# Revolution.net
KiCad netlist of a schematic drawn in Altium Designer
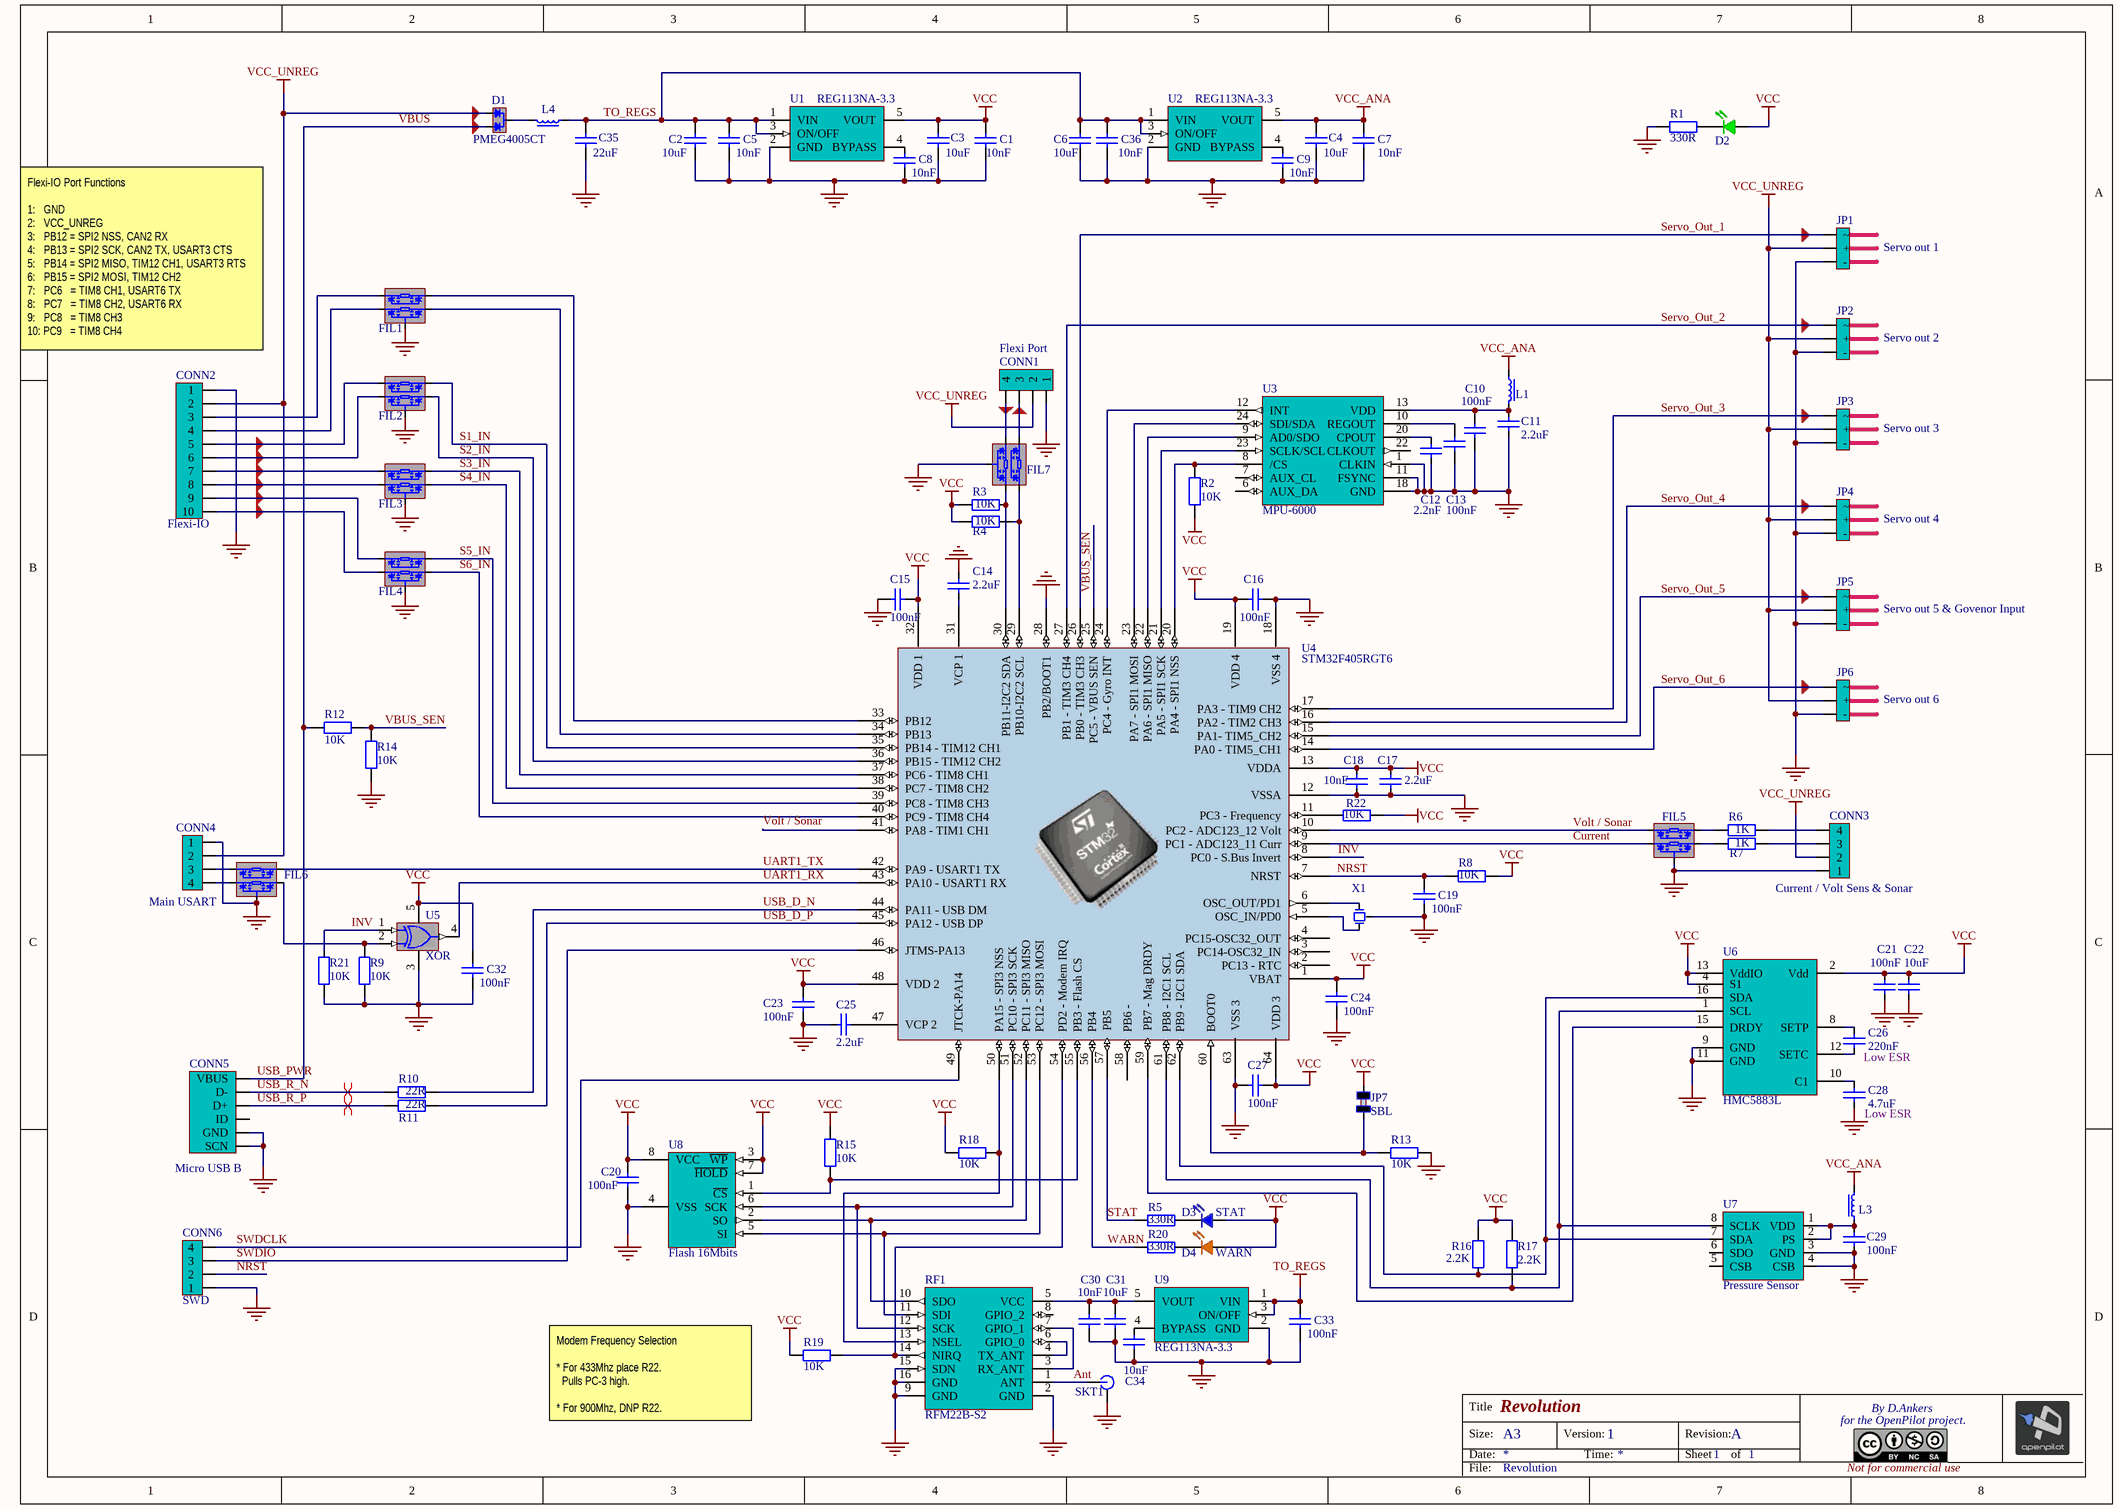
[diagram p0: Revolution.SchDoc]

(export (version "E")
  (design (tool "Eeschema 10.0.6"))
  (components
    (comp (ref "C1")
      (value "10nF")
      (footprint "CAP402N")
      (description "Capacitor SMD")
      (fields (field (name "Comment") "10n") (field (name "PUBLISHER") "The OpenPilot Project"))
      (libsource (lib "OpenPilot") (part "Cap402"))
    )
    (comp (ref "C2")
      (value "10uF")
      (footprint "CAP805L")
      (description "Capacitor SMD")
      (fields (field (name "Comment") "Cap805") (field (name "PUBLISHER") "The OpenPilot Project"))
      (libsource (lib "OpenPilot") (part "Cap805"))
    )
    (comp (ref "C3")
      (value "10uF")
      (footprint "CAP805L")
      (description "Capacitor SMD")
      (fields (field (name "Comment") "Cap805") (field (name "PUBLISHER") "The OpenPilot Project"))
      (libsource (lib "OpenPilot") (part "Cap805"))
    )
    (comp (ref "C4")
      (value "10uF")
      (footprint "CAP805L")
      (description "Capacitor SMD")
      (fields (field (name "Comment") "Cap805") (field (name "PUBLISHER") "The OpenPilot Project"))
      (libsource (lib "OpenPilot") (part "Cap805"))
    )
    (comp (ref "C5")
      (value "10nF")
      (footprint "CAP402N")
      (description "Capacitor SMD")
      (fields (field (name "Comment") "10n") (field (name "PUBLISHER") "The OpenPilot Project"))
      (libsource (lib "OpenPilot") (part "Cap402"))
    )
    (comp (ref "C6")
      (value "10uF")
      (footprint "CAP805L")
      (description "Capacitor SMD")
      (fields (field (name "Comment") "Cap805") (field (name "PUBLISHER") "The OpenPilot Project"))
      (libsource (lib "OpenPilot") (part "Cap805"))
    )
    (comp (ref "C7")
      (value "10nF")
      (footprint "CAP402N")
      (description "Capacitor SMD")
      (fields (field (name "Comment") "10n") (field (name "PUBLISHER") "The OpenPilot Project"))
      (libsource (lib "OpenPilot") (part "Cap402"))
    )
    (comp (ref "C8")
      (value "10nF")
      (footprint "CAP402N")
      (description "Capacitor SMD")
      (fields (field (name "Comment") "10n") (field (name "PUBLISHER") "The OpenPilot Project"))
      (libsource (lib "") (part "Cap402_1"))
    )
    (comp (ref "C9")
      (value "10nF")
      (footprint "CAP402N")
      (description "Capacitor SMD")
      (fields (field (name "Comment") "10n") (field (name "PUBLISHER") "The OpenPilot Project"))
      (libsource (lib "") (part "Cap402_1"))
    )
    (comp (ref "C10")
      (value "100nF")
      (footprint "CAP402N")
      (description "Capacitor SMD")
      (fields (field (name "Comment") "Cap402") (field (name "PUBLISHER") "The OpenPilot Project"))
      (libsource (lib "OpenPilot") (part "Cap402"))
    )
    (comp (ref "C11")
      (value "2.2uF")
      (footprint "CAP603L")
      (description "Capacitor SMD")
      (fields (field (name "Comment") "Cap603") (field (name "PUBLISHER") "The OpenPilot Project"))
      (libsource (lib "OpenPilot") (part "Cap603"))
    )
    (comp (ref "C12")
      (value "2.2nF")
      (footprint "CAP603L")
      (description "Capacitor SMD")
      (fields (field (name "Comment") "Cap603") (field (name "PUBLISHER") "The OpenPilot Project"))
      (libsource (lib "OpenPilot") (part "Cap603"))
    )
    (comp (ref "C13")
      (value "100nF")
      (footprint "CAP402N")
      (description "Capacitor SMD")
      (fields (field (name "Comment") "Cap402") (field (name "PUBLISHER") "The OpenPilot Project"))
      (libsource (lib "OpenPilot") (part "Cap402"))
    )
    (comp (ref "C14")
      (value "2.2uF")
      (footprint "CAP603L")
      (description "Capacitor SMD")
      (fields (field (name "Comment") "Cap603") (field (name "PUBLISHER") "The OpenPilot Project"))
      (libsource (lib "OpenPilot") (part "Cap603"))
    )
    (comp (ref "C15")
      (value "100nF")
      (footprint "CAP402N")
      (description "Capacitor SMD")
      (fields (field (name "Comment") "Cap402") (field (name "PUBLISHER") "The OpenPilot Project"))
      (libsource (lib "OpenPilot") (part "Cap402"))
    )
    (comp (ref "C16")
      (value "100nF")
      (footprint "CAP402N")
      (description "Capacitor SMD")
      (fields (field (name "Comment") "Cap402") (field (name "PUBLISHER") "The OpenPilot Project"))
      (libsource (lib "OpenPilot") (part "Cap402"))
    )
    (comp (ref "C17")
      (value "2.2uF")
      (footprint "CAP603L")
      (description "Capacitor SMD")
      (fields (field (name "Comment") "Cap603") (field (name "PUBLISHER") "The OpenPilot Project"))
      (libsource (lib "OpenPilot") (part "Cap603"))
    )
    (comp (ref "C18")
      (value "10nF")
      (footprint "CAP402N")
      (description "Capacitor SMD")
      (fields (field (name "Comment") "10n") (field (name "PUBLISHER") "The OpenPilot Project"))
      (libsource (lib "") (part "Cap402_2"))
    )
    (comp (ref "C19")
      (value "100nF")
      (footprint "CAP402N")
      (description "Capacitor SMD")
      (fields (field (name "Comment") "Cap402") (field (name "PUBLISHER") "The OpenPilot Project"))
      (libsource (lib "OpenPilot") (part "Cap402"))
    )
    (comp (ref "C20")
      (value "100nF")
      (footprint "CAP402N")
      (description "Capacitor SMD")
      (fields (field (name "Comment") "Cap402") (field (name "PUBLISHER") "The OpenPilot Project"))
      (libsource (lib "OpenPilot") (part "Cap402"))
    )
    (comp (ref "C21")
      (value "100nF")
      (footprint "CAP402N")
      (description "Capacitor SMD")
      (fields (field (name "Comment") "Cap402") (field (name "PUBLISHER") "The OpenPilot Project"))
      (libsource (lib "") (part "Cap402_2"))
    )
    (comp (ref "C22")
      (value "10uF")
      (footprint "CAP805L")
      (description "Capacitor SMD")
      (fields (field (name "Comment") "Cap805") (field (name "PUBLISHER") "The OpenPilot Project"))
      (libsource (lib "") (part "Cap805_1"))
    )
    (comp (ref "C23")
      (value "100nF")
      (footprint "CAP402N")
      (description "Capacitor SMD")
      (fields (field (name "Comment") "Cap402") (field (name "PUBLISHER") "The OpenPilot Project"))
      (libsource (lib "OpenPilot") (part "Cap402"))
    )
    (comp (ref "C24")
      (value "100nF")
      (footprint "CAP402N")
      (description "Capacitor SMD")
      (fields (field (name "Comment") "Cap402") (field (name "PUBLISHER") "The OpenPilot Project"))
      (libsource (lib "OpenPilot") (part "Cap402"))
    )
    (comp (ref "C25")
      (value "2.2uF")
      (footprint "CAP603L")
      (description "Capacitor SMD")
      (fields (field (name "Comment") "Cap603") (field (name "PUBLISHER") "The OpenPilot Project"))
      (libsource (lib "OpenPilot") (part "Cap603"))
    )
    (comp (ref "C26")
      (value "220nF")
      (footprint "CAP603L")
      (description "Capacitor SMD")
      (fields (field (name "Comment") "Cap603") (field (name "PUBLISHER") "The OpenPilot Project"))
      (libsource (lib "OpenPilot") (part "Cap603"))
    )
    (comp (ref "C27")
      (value "100nF")
      (footprint "CAP402N")
      (description "Capacitor SMD")
      (fields (field (name "Comment") "Cap402") (field (name "PUBLISHER") "The OpenPilot Project"))
      (libsource (lib "OpenPilot") (part "Cap402"))
    )
    (comp (ref "C28")
      (value "4.7uF")
      (footprint "CAP603L")
      (description "Capacitor SMD")
      (fields (field (name "Comment") "Cap603") (field (name "PUBLISHER") "The OpenPilot Project"))
      (libsource (lib "OpenPilot") (part "Cap603"))
    )
    (comp (ref "C29")
      (value "100nF")
      (footprint "CAP402N")
      (description "Capacitor SMD")
      (fields (field (name "Comment") "Cap402") (field (name "PUBLISHER") "The OpenPilot Project"))
      (libsource (lib "") (part "Cap402_2"))
    )
    (comp (ref "C30")
      (value "10nF")
      (footprint "CAP402N")
      (description "Capacitor SMD")
      (fields (field (name "Comment") "10n") (field (name "PUBLISHER") "The OpenPilot Project"))
      (libsource (lib "OpenPilot") (part "Cap402"))
    )
    (comp (ref "C31")
      (value "10uF")
      (footprint "CAP805L")
      (description "Capacitor SMD")
      (fields (field (name "Comment") "Cap805") (field (name "PUBLISHER") "The OpenPilot Project"))
      (libsource (lib "OpenPilot") (part "Cap805"))
    )
    (comp (ref "C32")
      (value "100nF")
      (footprint "CAP402N")
      (description "Capacitor SMD")
      (fields (field (name "Comment") "Cap402") (field (name "PUBLISHER") "The OpenPilot Project"))
      (libsource (lib "OpenPilot") (part "Cap402"))
    )
    (comp (ref "C33")
      (value "100nF")
      (footprint "CAP402N")
      (description "Capacitor SMD")
      (fields (field (name "Comment") "Cap402") (field (name "PUBLISHER") "The OpenPilot Project"))
      (libsource (lib "OpenPilot") (part "Cap402"))
    )
    (comp (ref "C34")
      (value "10nF")
      (footprint "CAP402N")
      (description "Capacitor SMD")
      (fields (field (name "Comment") "10n") (field (name "PUBLISHER") "The OpenPilot Project"))
      (libsource (lib "") (part "Cap402_1"))
    )
    (comp (ref "C35")
      (value "22uF")
      (footprint "CAP805L")
      (description "Capacitor SMD")
      (fields (field (name "Comment") "Cap805") (field (name "PUBLISHER") "The OpenPilot Project"))
      (libsource (lib "OpenPilot") (part "Cap805"))
    )
    (comp (ref "C36")
      (value "10nF")
      (footprint "CAP402N")
      (description "Capacitor SMD")
      (fields (field (name "Comment") "10n") (field (name "PUBLISHER") "The OpenPilot Project"))
      (libsource (lib "OpenPilot") (part "Cap402"))
    )
    (comp (ref "CONN1")
      (value "Flexi Port")
      (footprint "JST SH 4 Pin Side Entry")
      (description "JST-SH 4-pin Side Entry Socket")
      (fields (field (name "MANUFACTURER") "Generic Components"))
      (libsource (lib "") (part "JST-SH 4-pin Side Entry Socket_3"))
    )
    (comp (ref "CONN2")
      (value "Flexi-IO")
      (footprint "JST SH 10 PIN SIDE ENTRY")
      (description "JST-SH 10-pin Side Entry Socket")
      (fields (field (name "MANUFACTURER") "Generic Components"))
      (libsource (lib "OpenPilot") (part "JST-SH 10-pin Side Entry Socket"))
    )
    (comp (ref "CONN3")
      (value "Current / Volt Sens & Sonar")
      (footprint "JST SH 4 Pin Side Entry")
      (description "JST-SH 4-pin Side Entry Socket")
      (fields (field (name "MANUFACTURER") "Generic Components"))
      (libsource (lib "") (part "JST-SH 4-pin Side Entry Socket_2"))
    )
    (comp (ref "CONN4")
      (value "Main USART")
      (footprint "JST SH 4 Pin Side Entry")
      (description "JST-SH 4-pin Side Entry Socket")
      (fields (field (name "MANUFACTURER") "Generic Components"))
      (libsource (lib "") (part "JST-SH 4-pin Side Entry Socket_1"))
    )
    (comp (ref "CONN5")
      (value "Micro USB B")
      (footprint "Micro_USB")
      (description "USB Micro B SMT Socket")
      (fields (field (name "PUBLISHER") "The OpenPilot Project"))
      (libsource (lib "OpenPilot") (part "USB Micro B SMT"))
    )
    (comp (ref "CONN6")
      (value "SWD")
      (footprint "JST SH 4 Pin Side Entry")
      (description "JST-SH 4-pin Side Entry Socket")
      (fields (field (name "MANUFACTURER") "Generic Components"))
      (libsource (lib "OpenPilot") (part "JST-SH 4-pin Side Entry Socket"))
    )
    (comp (ref "D1")
      (value "PMEG4005CT")
      (footprint "SOT23-3N")
      (description "Dual Diode Command Cathode 500ma")
      (fields (field (name "PUBLISHER") "The OpenPilot Project"))
      (libsource (lib "OpenPilot") (part "PMEG4005CT"))
    )
    (comp (ref "D2")
      (value "Green")
      (footprint "LED603N")
      (description "Green 603 LED")
      (libsource (lib "OpenPilot") (part "LED 603 Gr"))
    )
    (comp (ref "D3")
      (value "STAT")
      (footprint "LED603N")
      (description "Blue 603 LED")
      (libsource (lib "OpenPilot") (part "LED 603 Bl"))
    )
    (comp (ref "D4")
      (value "WARN")
      (footprint "LED603N")
      (description "Orange 603 LED")
      (libsource (lib "OpenPilot") (part "LED 603 Or"))
    )
    (comp (ref "FIL1")
      (value "IP4256CZ5-W,115")
      (footprint "SOT-665")
      (description "IP4256CZ5-W,115 2 channel, 100R, 30pF, RF ESD Filter")
      (fields
        (field (name "MANUFACTURER") "Generic Components")
        (field (name "PUBLISHER") "The OpenPilot Project")
      )
      (libsource (lib "OpenPilot") (part "RF Filter 100R 30pF"))
    )
    (comp (ref "FIL2")
      (value "IP4256CZ5-W,115")
      (footprint "SOT-665")
      (description "IP4256CZ5-W,115 2 channel, 100R, 30pF, RF ESD Filter")
      (fields
        (field (name "MANUFACTURER") "Generic Components")
        (field (name "PUBLISHER") "The OpenPilot Project")
      )
      (libsource (lib "OpenPilot") (part "RF Filter 100R 30pF"))
    )
    (comp (ref "FIL3")
      (value "IP4256CZ5-W,115")
      (footprint "SOT-665")
      (description "IP4256CZ5-W,115 2 channel, 100R, 30pF, RF ESD Filter")
      (fields
        (field (name "MANUFACTURER") "Generic Components")
        (field (name "PUBLISHER") "The OpenPilot Project")
      )
      (libsource (lib "OpenPilot") (part "RF Filter 100R 30pF"))
    )
    (comp (ref "FIL4")
      (value "IP4256CZ5-W,115")
      (footprint "SOT-665")
      (description "IP4256CZ5-W,115 2 channel, 100R, 30pF, RF ESD Filter")
      (fields
        (field (name "MANUFACTURER") "Generic Components")
        (field (name "PUBLISHER") "The OpenPilot Project")
      )
      (libsource (lib "OpenPilot") (part "RF Filter 100R 30pF"))
    )
    (comp (ref "FIL5")
      (value "IP4256CZ5-W,115")
      (footprint "SOT-665")
      (description "IP4256CZ5-W,115 2 channel, 100R, 30pF, RF ESD Filter")
      (fields
        (field (name "MANUFACTURER") "Generic Components")
        (field (name "PUBLISHER") "The OpenPilot Project")
      )
      (libsource (lib "OpenPilot") (part "RF Filter 100R 30pF"))
    )
    (comp (ref "FIL6")
      (value "IP4256CZ5-W,115")
      (footprint "SOT-665")
      (description "IP4256CZ5-W,115 2 channel, 100R, 30pF, RF ESD Filter")
      (fields
        (field (name "MANUFACTURER") "Generic Components")
        (field (name "PUBLISHER") "The OpenPilot Project")
      )
      (libsource (lib "OpenPilot") (part "RF Filter 100R 30pF"))
    )
    (comp (ref "FIL7")
      (value "IP4256CZ5-W,115")
      (footprint "SOT-665")
      (description "IP4256CZ5-W,115 2 channel, 100R, 30pF, RF ESD Filter")
      (fields
        (field (name "MANUFACTURER") "Generic Components")
        (field (name "PUBLISHER") "The OpenPilot Project")
      )
      (libsource (lib "OpenPilot") (part "RF Filter 100R 30pF"))
    )
    (comp (ref "JP1")
      (value "Servo out 1")
      (footprint "SIP3 - 0.1")
      (description "Header, 3-Pin, 0.1\"")
      (fields (field (name "MANUFACTURER") "Generic Components"))
      (libsource (lib "OpenPilot") (part "Hdr 3 Pin 0.1"))
    )
    (comp (ref "JP2")
      (value "Servo out 2")
      (footprint "SIP3 - 0.1")
      (description "Header, 3-Pin, 0.1\"")
      (fields (field (name "MANUFACTURER") "Generic Components"))
      (libsource (lib "OpenPilot") (part "Hdr 3 Pin 0.1"))
    )
    (comp (ref "JP3")
      (value "Servo out 3")
      (footprint "SIP3 - 0.1")
      (description "Header, 3-Pin, 0.1\"")
      (fields (field (name "MANUFACTURER") "Generic Components"))
      (libsource (lib "OpenPilot") (part "Hdr 3 Pin 0.1"))
    )
    (comp (ref "JP4")
      (value "Servo out 4")
      (footprint "SIP3 - 0.1")
      (description "Header, 3-Pin, 0.1\"")
      (fields (field (name "MANUFACTURER") "Generic Components"))
      (libsource (lib "OpenPilot") (part "Hdr 3 Pin 0.1"))
    )
    (comp (ref "JP5")
      (value "Servo out 5 & Govenor Input")
      (footprint "SIP3 - 0.1")
      (description "Header, 3-Pin, 0.1\"")
      (fields (field (name "MANUFACTURER") "Generic Components"))
      (libsource (lib "OpenPilot") (part "Hdr 3 Pin 0.1"))
    )
    (comp (ref "JP6")
      (value "Servo out 6")
      (footprint "SIP3 - 0.1")
      (description "Header, 3-Pin, 0.1\"")
      (fields (field (name "MANUFACTURER") "Generic Components"))
      (libsource (lib "OpenPilot") (part "Hdr 3 Pin 0.1"))
    )
    (comp (ref "JP7")
      (value "SBL")
      (footprint "TOUCH JMP 2PAD")
      (description "2 Pad Touch Jumper")
      (fields (field (name "PUBLISHER") "The OpenPilot Project"))
      (libsource (lib "OpenPilot") (part "2 PAD Touch JMP"))
    )
    (comp (ref "L1")
      (value "FB 300mA")
      (footprint "IND603N")
      (description "Ferrite Bead 300mA")
      (fields
        (field (name "MANUFACTURER") "Generic Components")
        (field (name "PUBLISHER") "The OpenPilot Project")
      )
      (libsource (lib "OpenPilot") (part "FerriteBead 300mA"))
    )
    (comp (ref "L3")
      (value "FB 300mA")
      (footprint "IND603N")
      (description "Ferrite Bead 300mA")
      (fields
        (field (name "MANUFACTURER") "Generic Components")
        (field (name "PUBLISHER") "The OpenPilot Project")
      )
      (libsource (lib "OpenPilot") (part "FerriteBead 300mA"))
    )
    (comp (ref "L4")
      (value "FB 300mA")
      (footprint "IND603N")
      (description "Ferrite Bead 300mA")
      (fields
        (field (name "MANUFACTURER") "Generic Components")
        (field (name "PUBLISHER") "The OpenPilot Project")
      )
      (libsource (lib "OpenPilot") (part "FerriteBead 300mA"))
    )
    (comp (ref "R1")
      (value "330R")
      (footprint "RES402N")
      (description "Resistor SMD")
      (fields (field (name "Comment") "Res402") (field (name "PUBLISHER") "The OpenPilot Project"))
      (libsource (lib "") (part "Res402_1"))
    )
    (comp (ref "R2")
      (value "10K")
      (footprint "RES402N")
      (description "Resistor SMD")
      (fields (field (name "Comment") "Res402") (field (name "PUBLISHER") "The OpenPilot Project"))
      (libsource (lib "") (part "Res402_6"))
    )
    (comp (ref "R3")
      (value "10K")
      (footprint "RES402N")
      (description "Resistor SMD")
      (fields (field (name "Comment") "Res402") (field (name "PUBLISHER") "The OpenPilot Project"))
      (libsource (lib "") (part "Res402_5"))
    )
    (comp (ref "R4")
      (value "10K")
      (footprint "RES402N")
      (description "Resistor SMD")
      (fields (field (name "Comment") "Res402") (field (name "PUBLISHER") "The OpenPilot Project"))
      (libsource (lib "OpenPilot") (part "Res402"))
    )
    (comp (ref "R5")
      (value "330R")
      (footprint "RES402N")
      (description "Resistor SMD")
      (fields (field (name "Comment") "Res402") (field (name "PUBLISHER") "The OpenPilot Project"))
      (libsource (lib "OpenPilot") (part "Res402"))
    )
    (comp (ref "R6")
      (value "1K")
      (footprint "RES402N")
      (description "Resistor SMD")
      (fields (field (name "Comment") "Res402") (field (name "PUBLISHER") "The OpenPilot Project"))
      (libsource (lib "") (part "Res402_1"))
    )
    (comp (ref "R7")
      (value "1K")
      (footprint "RES402N")
      (description "Resistor SMD")
      (fields (field (name "Comment") "Res402") (field (name "PUBLISHER") "The OpenPilot Project"))
      (libsource (lib "") (part "Res402_1"))
    )
    (comp (ref "R8")
      (value "10K")
      (footprint "RES402N")
      (description "Resistor SMD")
      (fields (field (name "Comment") "Res402") (field (name "PUBLISHER") "The OpenPilot Project"))
      (libsource (lib "") (part "Res402_1"))
    )
    (comp (ref "R9")
      (value "10K")
      (footprint "RES402N")
      (description "Resistor SMD")
      (fields (field (name "Comment") "Res402") (field (name "PUBLISHER") "The OpenPilot Project"))
      (libsource (lib "") (part "Res402_6"))
    )
    (comp (ref "R10")
      (value "22R")
      (footprint "RES402N")
      (description "Resistor SMD")
      (fields (field (name "Comment") "Res402") (field (name "PUBLISHER") "The OpenPilot Project"))
      (libsource (lib "OpenPilot") (part "Res402"))
    )
    (comp (ref "R11")
      (value "22R")
      (footprint "RES402N")
      (description "Resistor SMD")
      (fields (field (name "Comment") "Res402") (field (name "PUBLISHER") "The OpenPilot Project"))
      (libsource (lib "OpenPilot") (part "Res402"))
    )
    (comp (ref "R12")
      (value "10K")
      (footprint "RES402N")
      (description "Resistor SMD")
      (fields (field (name "Comment") "Res402") (field (name "PUBLISHER") "The OpenPilot Project"))
      (libsource (lib "") (part "Res402_1"))
    )
    (comp (ref "R13")
      (value "10K")
      (footprint "RES402N")
      (description "Resistor SMD")
      (fields (field (name "Comment") "Res402") (field (name "PUBLISHER") "The OpenPilot Project"))
      (libsource (lib "") (part "Res402_1"))
    )
    (comp (ref "R14")
      (value "10K")
      (footprint "RES402N")
      (description "Resistor SMD")
      (fields (field (name "Comment") "Res402") (field (name "PUBLISHER") "The OpenPilot Project"))
      (libsource (lib "") (part "Res402_6"))
    )
    (comp (ref "R15")
      (value "10K")
      (footprint "RES402N")
      (description "Resistor SMD")
      (fields (field (name "Comment") "Res402") (field (name "PUBLISHER") "The OpenPilot Project"))
      (libsource (lib "") (part "Res402_4"))
    )
    (comp (ref "R16")
      (value "2.2K")
      (footprint "RES402N")
      (description "Resistor SMD")
      (fields (field (name "Comment") "Res402") (field (name "PUBLISHER") "The OpenPilot Project"))
      (libsource (lib "") (part "Res402_2"))
    )
    (comp (ref "R17")
      (value "2.2K")
      (footprint "RES402N")
      (description "Resistor SMD")
      (fields (field (name "Comment") "Res402") (field (name "PUBLISHER") "The OpenPilot Project"))
      (libsource (lib "") (part "Res402_4"))
    )
    (comp (ref "R18")
      (value "10K")
      (footprint "RES402N")
      (description "Resistor SMD")
      (fields (field (name "Comment") "Res402") (field (name "PUBLISHER") "The OpenPilot Project"))
      (libsource (lib "") (part "Res402_1"))
    )
    (comp (ref "R19")
      (value "10K")
      (footprint "RES402N")
      (description "Resistor SMD")
      (fields (field (name "Comment") "Res402") (field (name "PUBLISHER") "The OpenPilot Project"))
      (libsource (lib "OpenPilot") (part "Res402"))
    )
    (comp (ref "R20")
      (value "330R")
      (footprint "RES402N")
      (description "Resistor SMD")
      (fields (field (name "Comment") "Res402") (field (name "PUBLISHER") "The OpenPilot Project"))
      (libsource (lib "OpenPilot") (part "Res402"))
    )
    (comp (ref "R21")
      (value "10K")
      (footprint "RES402N")
      (description "Resistor SMD")
      (fields (field (name "Comment") "Res402") (field (name "PUBLISHER") "The OpenPilot Project"))
      (libsource (lib "") (part "Res402_3"))
    )
    (comp (ref "R22")
      (value "10K")
      (footprint "RES402N")
      (description "Resistor SMD")
      (fields (field (name "Comment") "Res402") (field (name "PUBLISHER") "The OpenPilot Project"))
      (libsource (lib "OpenPilot") (part "Res402"))
    )
    (comp (ref "RF1")
      (value "RFM22B-S2")
      (footprint "RFM22-S2")
      (description "UHF 100mW Transceiver")
      (libsource (lib "OpenPilot") (part "RFM22B-S2"))
    )
    (comp (ref "SKT1")
      (value "MMCX Thru hole")
      (footprint "MMCX_SOCKET")
      (description "MMCX Socket")
      (libsource (lib "OpenPilot") (part "MMCX Thru hole"))
    )
    (comp (ref "U1")
      (value "REG113NA-3.3")
      (footprint "SOT23-5L")
      (description "3.3V 400mA LDO Regulator")
      (libsource (lib "OpenPilot") (part "REG113NA-3.3"))
    )
    (comp (ref "U2")
      (value "REG113NA-3.3")
      (footprint "SOT23-5L")
      (description "3.3V 400mA LDO Regulator")
      (libsource (lib "OpenPilot") (part "REG113NA-3.3"))
    )
    (comp (ref "U3")
      (value "MPU-6000")
      (footprint "IMU-3000")
      (description "Invensense MPU-3/6000,  3-axis Gyros & Accel on 6000")
      (fields (field (name "MANUFACTURER") "Invensense") (field (name "PUBLISHER") "The OpenPilot Project"))
      (libsource (lib "OpenPilot") (part "MPU-3/6000"))
    )
    (comp (ref "U4")
      (value "STM32F405RGT6")
      (footprint "STM32 64 Lead")
      (description "STM32 ARM-based 32-bit MCU with 1MB Flash, 64-pin LQFP, Industrial Temperature")
      (libsource (lib "OpenPilot") (part "STM32F103RET6"))
    )
    (comp (ref "U5")
      (value "XOR")
      (footprint "DCK-5")
      (description "XOR Gate SN74LVC1G86DCKR")
      (libsource (lib "OpenPilot") (part "XOR SN74LVC1G86DCKR"))
    )
    (comp (ref "U6")
      (value "HMC5883L")
      (footprint "LPCC-16")
      (description "IC, Magnetometer, 3 axis, +/- 8 Oe, I2C, 160Hz")
      (fields (field (name "MANUFACTURER") "Honeywell") (field (name "PUBLISHER") "The OpenPilot Project"))
      (libsource (lib "OpenPilot") (part "HMC5883L"))
    )
    (comp (ref "U7")
      (value "Pressure Sensor")
      (footprint "MS5611-01BA03")
      (description "Pressure Sensor - MS5611-01BA03")
      (libsource (lib "OpenPilot") (part "MS5611-01BA03"))
    )
    (comp (ref "U8")
      (value "Flash 16Mbits")
      (footprint "SOIC8_N")
      (description "16Mbit SPI Flash Memory")
      (fields (field (name "PUBLISHER") "The OpenPilot Project"))
      (libsource (lib "OpenPilot") (part "Flash 16Mb 75MHZ 8SOIC"))
    )
    (comp (ref "U9")
      (value "REG113NA-3.3")
      (footprint "SOT23-5L")
      (description "3.3V 400mA LDO Regulator")
      (libsource (lib "") (part "REG113NA-3.3_1"))
    )
    (comp (ref "X1")
      (value "8Mhz Ceralock")
      (footprint "CERALOCK 8Mhz")
      (description "Ceralock 8Mhz with caps")
      (fields (field (name "PUBLISHER") "The OpenPilot Project"))
      (libsource (lib "OpenPilot") (part "CERALOCK8"))
    )
  )
  (nets
    (net (code "1") (name "/Ant") (class "Default")
      (node (ref "RF1") (pin "1") (pinfunction "ANT_1") (pintype "passive"))
      (node (ref "SKT1") (pin "1") (pinfunction "PIN_1") (pintype "passive"))
    )
    (net (code "2") (name "/Current") (class "Default")
      (node (ref "FIL5") (pin "1") (pinfunction "1_1") (pintype "passive"))
      (node (ref "U4") (pin "9") (pinfunction "PC1_-_ADC123_11_Curr_9") (pintype "bidirectional"))
    )
    (net (code "3") (name "/INV") (class "Default")
      (node (ref "R21") (pin "2") (pinfunction "2_2") (pintype "passive"))
      (node (ref "U4") (pin "8") (pinfunction "PC0_-_S.Bus_Invert_8") (pintype "bidirectional"))
      (node (ref "U5") (pin "1") (pinfunction "A_1") (pintype "input"))
    )
    (net (code "4") (name "/NRST") (class "Default")
      (node (ref "C19") (pin "2") (pinfunction "2_2") (pintype "passive"))
      (node (ref "CONN6") (pin "2") (pinfunction "2_2") (pintype "passive"))
      (node (ref "R8") (pin "1") (pinfunction "1_1") (pintype "passive"))
      (node (ref "U4") (pin "7") (pinfunction "NRST_7") (pintype "bidirectional"))
    )
    (net (code "5") (name "/S1_IN") (class "Default")
      (node (ref "FIL2") (pin "3") (pinfunction "3_3") (pintype "passive"))
      (node (ref "U4") (pin "35") (pinfunction "PB14_-_TIM12_CH1_35") (pintype "bidirectional"))
    )
    (net (code "6") (name "/S2_IN") (class "Default")
      (node (ref "FIL2") (pin "1") (pinfunction "1_1") (pintype "passive"))
      (node (ref "U4") (pin "36") (pinfunction "PB15_-_TIM12_CH2_36") (pintype "bidirectional"))
    )
    (net (code "7") (name "/S3_IN") (class "Default")
      (node (ref "FIL3") (pin "3") (pinfunction "3_3") (pintype "passive"))
      (node (ref "U4") (pin "37") (pinfunction "PC6_-_TIM8_CH1_37") (pintype "bidirectional"))
    )
    (net (code "8") (name "/S4_IN") (class "Default")
      (node (ref "FIL3") (pin "1") (pinfunction "1_1") (pintype "passive"))
      (node (ref "U4") (pin "38") (pinfunction "PC7_-_TIM8_CH2_38") (pintype "bidirectional"))
    )
    (net (code "9") (name "/S5_IN") (class "Default")
      (node (ref "FIL4") (pin "3") (pinfunction "3_3") (pintype "passive"))
      (node (ref "U4") (pin "39") (pinfunction "PC8_-_TIM8_CH3_39") (pintype "bidirectional"))
    )
    (net (code "10") (name "/S6_IN") (class "Default")
      (node (ref "FIL4") (pin "1") (pinfunction "1_1") (pintype "passive"))
      (node (ref "U4") (pin "40") (pinfunction "PC9_-_TIM8_CH4_40") (pintype "bidirectional"))
    )
    (net (code "11") (name "/STAT") (class "Default")
      (node (ref "R5") (pin "2") (pinfunction "2_2") (pintype "passive"))
      (node (ref "U4") (pin "57") (pinfunction "PB5_57") (pintype "bidirectional"))
    )
    (net (code "12") (name "/SWDCLK") (class "Default")
      (node (ref "CONN6") (pin "4") (pinfunction "4_4") (pintype "passive"))
      (node (ref "U4") (pin "49") (pinfunction "JTCK-PA14_49") (pintype "bidirectional"))
    )
    (net (code "13") (name "/SWDIO") (class "Default")
      (node (ref "CONN6") (pin "3") (pinfunction "3_3") (pintype "passive"))
      (node (ref "U4") (pin "46") (pinfunction "JTMS-PA13_46") (pintype "bidirectional"))
    )
    (net (code "14") (name "/Servo_Out_1") (class "Default")
      (node (ref "JP1") (pin "1") (pinfunction "~_1") (pintype "passive"))
      (node (ref "U4") (pin "26") (pinfunction "PB0_-_TIM3_CH3_26") (pintype "bidirectional"))
    )
    (net (code "15") (name "/Servo_Out_2") (class "Default")
      (node (ref "JP2") (pin "1") (pinfunction "~_1") (pintype "passive"))
      (node (ref "U4") (pin "27") (pinfunction "PB1_-_TIM3_CH4_27") (pintype "bidirectional"))
    )
    (net (code "16") (name "/Servo_Out_3") (class "Default")
      (node (ref "JP3") (pin "1") (pinfunction "~_1") (pintype "passive"))
      (node (ref "U4") (pin "17") (pinfunction "PA3_-_TIM9_CH2_17") (pintype "bidirectional"))
    )
    (net (code "17") (name "/Servo_Out_4") (class "Default")
      (node (ref "JP4") (pin "1") (pinfunction "~_1") (pintype "passive"))
      (node (ref "U4") (pin "16") (pinfunction "PA2_-_TIM2_CH3_16") (pintype "bidirectional"))
    )
    (net (code "18") (name "/Servo_Out_5") (class "Default")
      (node (ref "JP5") (pin "1") (pinfunction "~_1") (pintype "passive"))
      (node (ref "U4") (pin "15") (pinfunction "PA1-_TIM5_CH2_15") (pintype "bidirectional"))
    )
    (net (code "19") (name "/Servo_Out_6") (class "Default")
      (node (ref "JP6") (pin "1") (pinfunction "~_1") (pintype "passive"))
      (node (ref "U4") (pin "14") (pinfunction "PA0_-_TIM5_CH1_14") (pintype "bidirectional"))
    )
    (net (code "20") (name "/UART1_RX") (class "Default")
      (node (ref "U4") (pin "43") (pinfunction "PA10_-_USART1_RX_43") (pintype "bidirectional"))
      (node (ref "U5") (pin "4") (pinfunction "Y_4") (pintype "output"))
    )
    (net (code "21") (name "/UART1_TX") (class "Default")
      (node (ref "FIL6") (pin "3") (pinfunction "3_3") (pintype "passive"))
      (node (ref "U4") (pin "42") (pinfunction "PA9_-_USART1_TX_42") (pintype "bidirectional"))
    )
    (net (code "22") (name "/USB_D_N") (class "Default")
      (node (ref "R10") (pin "1") (pinfunction "1_1") (pintype "passive"))
      (node (ref "U4") (pin "44") (pinfunction "PA11_-_USB_DM_44") (pintype "bidirectional"))
    )
    (net (code "23") (name "/USB_D_P") (class "Default")
      (node (ref "R11") (pin "1") (pinfunction "1_1") (pintype "passive"))
      (node (ref "U4") (pin "45") (pinfunction "PA12_-_USB_DP_45") (pintype "bidirectional"))
    )
    (net (code "24") (name "/USB_PWR") (class "Default")
      (node (ref "CONN5") (pin "1") (pinfunction "VBUS_1") (pintype "passive"))
      (node (ref "D1") (pin "1") (pinfunction "A1_1") (pintype "passive"))
      (node (ref "R12") (pin "1") (pinfunction "1_1") (pintype "passive"))
    )
    (net (code "25") (name "/USB_R_N") (class "Default")
      (node (ref "CONN5") (pin "2") (pinfunction "D-_2") (pintype "passive"))
      (node (ref "R10") (pin "2") (pinfunction "2_2") (pintype "passive"))
    )
    (net (code "26") (name "/USB_R_P") (class "Default")
      (node (ref "CONN5") (pin "3") (pinfunction "D+_3") (pintype "passive"))
      (node (ref "R11") (pin "2") (pinfunction "2_2") (pintype "passive"))
    )
    (net (code "27") (name "/VBUS_SEN") (class "Default")
      (node (ref "R12") (pin "2") (pinfunction "2_2") (pintype "passive"))
      (node (ref "R14") (pin "2") (pinfunction "2_2") (pintype "passive"))
      (node (ref "U4") (pin "25") (pinfunction "PC5_-_VBUS_SEN_25") (pintype "bidirectional"))
    )
    (net (code "28") (name "/Volt {slash} Sonar") (class "Default")
      (node (ref "FIL5") (pin "3") (pinfunction "3_3") (pintype "passive"))
      (node (ref "U4") (pin "10") (pinfunction "PC2_-_ADC123_12_Volt_10") (pintype "bidirectional"))
      (node (ref "U4") (pin "41") (pinfunction "PA8_-_TIM1_CH1_41") (pintype "bidirectional"))
    )
    (net (code "29") (name "/WARN") (class "Default")
      (node (ref "R20") (pin "2") (pinfunction "2_2") (pintype "passive"))
      (node (ref "U4") (pin "56") (pinfunction "PB4_56") (pintype "bidirectional"))
    )
    (net (code "30") (name "GND") (class "Default")
      (node (ref "C1") (pin "2") (pinfunction "2_2") (pintype "passive"))
      (node (ref "C10") (pin "1") (pinfunction "1_1") (pintype "passive"))
      (node (ref "C11") (pin "2") (pinfunction "2_2") (pintype "passive"))
      (node (ref "C12") (pin "1") (pinfunction "1_1") (pintype "passive"))
      (node (ref "C13") (pin "2") (pinfunction "2_2") (pintype "passive"))
      (node (ref "C14") (pin "1") (pinfunction "1_1") (pintype "passive"))
      (node (ref "C15") (pin "2") (pinfunction "2_2") (pintype "passive"))
      (node (ref "C16") (pin "1") (pinfunction "1_1") (pintype "passive"))
      (node (ref "C17") (pin "1") (pinfunction "1_1") (pintype "passive"))
      (node (ref "C18") (pin "2") (pinfunction "2_2") (pintype "passive"))
      (node (ref "C19") (pin "1") (pinfunction "1_1") (pintype "passive"))
      (node (ref "C2") (pin "2") (pinfunction "2_2") (pintype "passive"))
      (node (ref "C20") (pin "1") (pinfunction "1_1") (pintype "passive"))
      (node (ref "C21") (pin "2") (pinfunction "2_2") (pintype "passive"))
      (node (ref "C22") (pin "1") (pinfunction "1_1") (pintype "passive"))
      (node (ref "C23") (pin "2") (pinfunction "2_2") (pintype "passive"))
      (node (ref "C24") (pin "1") (pinfunction "1_1") (pintype "passive"))
      (node (ref "C25") (pin "1") (pinfunction "1_1") (pintype "passive"))
      (node (ref "C27") (pin "2") (pinfunction "2_2") (pintype "passive"))
      (node (ref "C28") (pin "2") (pinfunction "2_2") (pintype "passive"))
      (node (ref "C29") (pin "2") (pinfunction "2_2") (pintype "passive"))
      (node (ref "C3") (pin "2") (pinfunction "2_2") (pintype "passive"))
      (node (ref "C30") (pin "2") (pinfunction "2_2") (pintype "passive"))
      (node (ref "C31") (pin "2") (pinfunction "2_2") (pintype "passive"))
      (node (ref "C32") (pin "2") (pinfunction "2_2") (pintype "passive"))
      (node (ref "C33") (pin "1") (pinfunction "1_1") (pintype "passive"))
      (node (ref "C34") (pin "2") (pinfunction "2_2") (pintype "passive"))
      (node (ref "C35") (pin "2") (pinfunction "2_2") (pintype "passive"))
      (node (ref "C36") (pin "2") (pinfunction "2_2") (pintype "passive"))
      (node (ref "C4") (pin "2") (pinfunction "2_2") (pintype "passive"))
      (node (ref "C5") (pin "2") (pinfunction "2_2") (pintype "passive"))
      (node (ref "C6") (pin "2") (pinfunction "2_2") (pintype "passive"))
      (node (ref "C7") (pin "2") (pinfunction "2_2") (pintype "passive"))
      (node (ref "C8") (pin "2") (pinfunction "2_2") (pintype "passive"))
      (node (ref "C9") (pin "2") (pinfunction "2_2") (pintype "passive"))
      (node (ref "CONN1") (pin "1") (pinfunction "1_1") (pintype "passive"))
      (node (ref "CONN2") (pin "1") (pinfunction "1_1") (pintype "passive"))
      (node (ref "CONN3") (pin "1") (pinfunction "1_1") (pintype "passive"))
      (node (ref "CONN4") (pin "1") (pinfunction "1_1") (pintype "passive"))
      (node (ref "CONN5") (pin "0") (pinfunction "SCN_0") (pintype "passive"))
      (node (ref "CONN5") (pin "5") (pinfunction "GND_5") (pintype "passive"))
      (node (ref "CONN6") (pin "1") (pinfunction "1_1") (pintype "passive"))
      (node (ref "FIL1") (pin "2") (pinfunction "PAD_2") (pintype "passive"))
      (node (ref "FIL2") (pin "2") (pinfunction "PAD_2") (pintype "passive"))
      (node (ref "FIL3") (pin "2") (pinfunction "PAD_2") (pintype "passive"))
      (node (ref "FIL4") (pin "2") (pinfunction "PAD_2") (pintype "passive"))
      (node (ref "FIL5") (pin "2") (pinfunction "PAD_2") (pintype "passive"))
      (node (ref "FIL6") (pin "2") (pinfunction "PAD_2") (pintype "passive"))
      (node (ref "FIL7") (pin "2") (pinfunction "PAD_2") (pintype "passive"))
      (node (ref "JP1") (pin "3") (pinfunction "-_3") (pintype "passive"))
      (node (ref "JP2") (pin "3") (pinfunction "-_3") (pintype "passive"))
      (node (ref "JP3") (pin "3") (pinfunction "-_3") (pintype "passive"))
      (node (ref "JP4") (pin "3") (pinfunction "-_3") (pintype "passive"))
      (node (ref "JP5") (pin "3") (pinfunction "-_3") (pintype "passive"))
      (node (ref "JP6") (pin "3") (pinfunction "-_3") (pintype "passive"))
      (node (ref "R1") (pin "1") (pinfunction "1_1") (pintype "passive"))
      (node (ref "R13") (pin "2") (pinfunction "2_2") (pintype "passive"))
      (node (ref "R14") (pin "1") (pinfunction "1_1") (pintype "passive"))
      (node (ref "R21") (pin "1") (pinfunction "1_1") (pintype "passive"))
      (node (ref "R9") (pin "1") (pinfunction "1_1") (pintype "passive"))
      (node (ref "RF1") (pin "15") (pinfunction "SDN_15") (pintype "input"))
      (node (ref "RF1") (pin "16") (pinfunction "GND_16") (pintype "power_in"))
      (node (ref "RF1") (pin "2") (pinfunction "GND_2") (pintype "power_in"))
      (node (ref "RF1") (pin "9") (pinfunction "GND_9") (pintype "power_in"))
      (node (ref "SKT1") (pin "2") (pinfunction "GND_2") (pintype "passive"))
      (node (ref "U1") (pin "2") (pinfunction "GND_2") (pintype "power_in"))
      (node (ref "U2") (pin "2") (pinfunction "GND_2") (pintype "power_in"))
      (node (ref "U3") (pin "1") (pinfunction "CLKIN_1") (pintype "input"))
      (node (ref "U3") (pin "11") (pinfunction "FSYNC_11") (pintype "passive"))
      (node (ref "U3") (pin "18") (pinfunction "GND_18") (pintype "power_in"))
      (node (ref "U4") (pin "12") (pinfunction "VSSA_12") (pintype "power_in"))
      (node (ref "U4") (pin "18") (pinfunction "VSS_4_18") (pintype "power_in"))
      (node (ref "U4") (pin "28") (pinfunction "PB2/BOOT1_28") (pintype "bidirectional"))
      (node (ref "U4") (pin "63") (pinfunction "VSS_3_63") (pintype "power_in"))
      (node (ref "U5") (pin "3") (pinfunction "GND_3") (pintype "power_in"))
      (node (ref "U6") (pin "11") (pinfunction "GND_11") (pintype "passive"))
      (node (ref "U6") (pin "9") (pinfunction "GND_9") (pintype "passive"))
      (node (ref "U7") (pin "3") (pinfunction "GND_3") (pintype "power_in"))
      (node (ref "U7") (pin "4") (pinfunction "CSB_4") (pintype "passive"))
      (node (ref "U8") (pin "4") (pinfunction "VSS_4") (pintype "power_in"))
      (node (ref "U9") (pin "2") (pinfunction "GND_2") (pintype "power_in"))
      (node (ref "X1") (pin "3") (pinfunction "3_3") (pintype "passive"))
    )
    (net (code "31") (name "Net-(CONN1-Pad3)") (class "Default")
      (node (ref "CONN1") (pin "3") (pinfunction "3_3") (pintype "passive"))
      (node (ref "FIL7") (pin "4") (pinfunction "4_4") (pintype "passive"))
    )
    (net (code "32") (name "Net-(CONN1-Pad4)") (class "Default")
      (node (ref "CONN1") (pin "4") (pinfunction "4_4") (pintype "passive"))
      (node (ref "FIL7") (pin "5") (pinfunction "5_5") (pintype "passive"))
    )
    (net (code "33") (name "Net-(CONN2-Pad3)") (class "Default")
      (node (ref "CONN2") (pin "3") (pinfunction "3_3") (pintype "passive"))
      (node (ref "FIL1") (pin "4") (pinfunction "4_4") (pintype "passive"))
    )
    (net (code "34") (name "Net-(CONN2-Pad4)") (class "Default")
      (node (ref "CONN2") (pin "4") (pinfunction "4_4") (pintype "passive"))
      (node (ref "FIL1") (pin "5") (pinfunction "5_5") (pintype "passive"))
    )
    (net (code "35") (name "Net-(CONN2-Pad5)") (class "Default")
      (node (ref "CONN2") (pin "5") (pinfunction "5_5") (pintype "passive"))
      (node (ref "FIL2") (pin "4") (pinfunction "4_4") (pintype "passive"))
    )
    (net (code "36") (name "Net-(CONN2-Pad6)") (class "Default")
      (node (ref "CONN2") (pin "6") (pinfunction "6_6") (pintype "passive"))
      (node (ref "FIL2") (pin "5") (pinfunction "5_5") (pintype "passive"))
    )
    (net (code "37") (name "Net-(CONN2-Pad7)") (class "Default")
      (node (ref "CONN2") (pin "7") (pinfunction "7_7") (pintype "passive"))
      (node (ref "FIL3") (pin "4") (pinfunction "4_4") (pintype "passive"))
    )
    (net (code "38") (name "Net-(CONN2-Pad8)") (class "Default")
      (node (ref "CONN2") (pin "8") (pinfunction "8_8") (pintype "passive"))
      (node (ref "FIL3") (pin "5") (pinfunction "5_5") (pintype "passive"))
    )
    (net (code "39") (name "Net-(CONN2-Pad9)") (class "Default")
      (node (ref "CONN2") (pin "9") (pinfunction "9_9") (pintype "passive"))
      (node (ref "FIL4") (pin "4") (pinfunction "4_4") (pintype "passive"))
    )
    (net (code "40") (name "Net-(CONN2-Pad10)") (class "Default")
      (node (ref "CONN2") (pin "10") (pinfunction "10_10") (pintype "passive"))
      (node (ref "FIL4") (pin "5") (pinfunction "5_5") (pintype "passive"))
    )
    (net (code "41") (name "Net-(CONN3-Pad3)") (class "Default")
      (node (ref "CONN3") (pin "3") (pinfunction "3_3") (pintype "passive"))
      (node (ref "R7") (pin "2") (pinfunction "2_2") (pintype "passive"))
    )
    (net (code "42") (name "Net-(CONN3-Pad4)") (class "Default")
      (node (ref "CONN3") (pin "4") (pinfunction "4_4") (pintype "passive"))
      (node (ref "R6") (pin "2") (pinfunction "2_2") (pintype "passive"))
    )
    (net (code "43") (name "Net-(CONN4-Pad3)") (class "Default")
      (node (ref "CONN4") (pin "3") (pinfunction "3_3") (pintype "passive"))
      (node (ref "FIL6") (pin "4") (pinfunction "4_4") (pintype "passive"))
    )
    (net (code "44") (name "Net-(CONN4-Pad4)") (class "Default")
      (node (ref "CONN4") (pin "4") (pinfunction "4_4") (pintype "passive"))
      (node (ref "FIL6") (pin "5") (pinfunction "5_5") (pintype "passive"))
    )
    (net (code "45") (name "Net-(D1-COM)") (class "Default")
      (node (ref "D1") (pin "3") (pinfunction "COM_3") (pintype "passive"))
      (node (ref "L4") (pin "2") (pinfunction "2_2") (pintype "passive"))
    )
    (net (code "46") (name "Net-(D2-K)") (class "Default")
      (node (ref "D2") (pin "1") (pinfunction "K_1") (pintype "passive"))
      (node (ref "R1") (pin "2") (pinfunction "2_2") (pintype "passive"))
    )
    (net (code "47") (name "Net-(D3-K)") (class "Default")
      (node (ref "D3") (pin "1") (pinfunction "K_1") (pintype "passive"))
      (node (ref "R5") (pin "1") (pinfunction "1_1") (pintype "passive"))
    )
    (net (code "48") (name "Net-(D4-K)") (class "Default")
      (node (ref "D4") (pin "1") (pinfunction "K_1") (pintype "passive"))
      (node (ref "R20") (pin "1") (pinfunction "1_1") (pintype "passive"))
    )
    (net (code "49") (name "Net-(FIL5-Pad4)") (class "Default")
      (node (ref "FIL5") (pin "4") (pinfunction "4_4") (pintype "passive"))
      (node (ref "R6") (pin "1") (pinfunction "1_1") (pintype "passive"))
    )
    (net (code "50") (name "Net-(FIL5-Pad5)") (class "Default")
      (node (ref "FIL5") (pin "5") (pinfunction "5_5") (pintype "passive"))
      (node (ref "R7") (pin "1") (pinfunction "1_1") (pintype "passive"))
    )
    (net (code "51") (name "Net-(RF1-GPIO_0)") (class "Default")
      (node (ref "RF1") (pin "4") (pinfunction "TX_ANT_4") (pintype "passive"))
      (node (ref "RF1") (pin "6") (pinfunction "GPIO_0_6") (pintype "bidirectional"))
    )
    (net (code "52") (name "Net-(RF1-GPIO_1)") (class "Default")
      (node (ref "RF1") (pin "3") (pinfunction "RX_ANT_3") (pintype "passive"))
      (node (ref "RF1") (pin "7") (pinfunction "GPIO_1_7") (pintype "bidirectional"))
    )
    (net (code "53") (name "Net-(RF1-NIRQ)") (class "Default")
      (node (ref "R19") (pin "1") (pinfunction "1_1") (pintype "passive"))
      (node (ref "RF1") (pin "14") (pinfunction "NIRQ_14") (pintype "output"))
      (node (ref "U4") (pin "54") (pinfunction "PD2_-_Modem_IRQ_54") (pintype "bidirectional"))
    )
    (net (code "54") (name "Net-(RF1-NSEL)") (class "Default")
      (node (ref "R18") (pin "2") (pinfunction "2_2") (pintype "passive"))
      (node (ref "RF1") (pin "13") (pinfunction "NSEL_13") (pintype "input"))
      (node (ref "U4") (pin "50") (pinfunction "PA15_-_SPI3_NSS_50") (pintype "bidirectional"))
    )
    (net (code "55") (name "Net-(RF1-SCK)") (class "Default")
      (node (ref "RF1") (pin "12") (pinfunction "SCK_12") (pintype "input"))
      (node (ref "U4") (pin "51") (pinfunction "PC10_-_SPI3_SCK_51") (pintype "bidirectional"))
      (node (ref "U8") (pin "6") (pinfunction "SCK_6") (pintype "input"))
    )
    (net (code "56") (name "Net-(RF1-SDI)") (class "Default")
      (node (ref "RF1") (pin "11") (pinfunction "SDI_11") (pintype "input"))
      (node (ref "U4") (pin "53") (pinfunction "PC12_-_SPI3_MOSI_53") (pintype "bidirectional"))
      (node (ref "U8") (pin "5") (pinfunction "SI_5") (pintype "input"))
    )
    (net (code "57") (name "Net-(RF1-SDO)") (class "Default")
      (node (ref "RF1") (pin "10") (pinfunction "SDO_10") (pintype "output"))
      (node (ref "U4") (pin "52") (pinfunction "PC11_-_SPI3_MISO_52") (pintype "bidirectional"))
      (node (ref "U8") (pin "2") (pinfunction "SO_2") (pintype "output"))
    )
    (net (code "58") (name "Net-(RF1-VCC)") (class "Default")
      (node (ref "C30") (pin "1") (pinfunction "1_1") (pintype "passive"))
      (node (ref "C31") (pin "1") (pinfunction "1_1") (pintype "passive"))
      (node (ref "RF1") (pin "5") (pinfunction "VCC_5") (pintype "power_in"))
      (node (ref "U9") (pin "5") (pinfunction "VOUT_5") (pintype "power_in"))
    )
    (net (code "59") (name "Net-(U1-BYPASS)") (class "Default")
      (node (ref "C8") (pin "1") (pinfunction "1_1") (pintype "passive"))
      (node (ref "U1") (pin "4") (pinfunction "BYPASS_4") (pintype "passive"))
    )
    (net (code "60") (name "Net-(U2-BYPASS)") (class "Default")
      (node (ref "C9") (pin "1") (pinfunction "1_1") (pintype "passive"))
      (node (ref "U2") (pin "4") (pinfunction "BYPASS_4") (pintype "passive"))
    )
    (net (code "61") (name "Net-(U3-AD0{slash}SDO)") (class "Default")
      (node (ref "U3") (pin "9") (pinfunction "AD0/SDO_9") (pintype "input"))
      (node (ref "U4") (pin "22") (pinfunction "PA6_-_SPI1_MISO_22") (pintype "bidirectional"))
    )
    (net (code "62") (name "Net-(U3-CPOUT)") (class "Default")
      (node (ref "C12") (pin "2") (pinfunction "2_2") (pintype "passive"))
      (node (ref "U3") (pin "20") (pinfunction "CPOUT_20") (pintype "passive"))
    )
    (net (code "63") (name "Net-(U3-INT)") (class "Default")
      (node (ref "U3") (pin "12") (pinfunction "INT_12") (pintype "output"))
      (node (ref "U4") (pin "24") (pinfunction "PC4_-_Gyro_INT_24") (pintype "bidirectional"))
    )
    (net (code "64") (name "Net-(U3-REGOUT)") (class "Default")
      (node (ref "C13") (pin "1") (pinfunction "1_1") (pintype "passive"))
      (node (ref "U3") (pin "10") (pinfunction "REGOUT_10") (pintype "passive"))
    )
    (net (code "65") (name "Net-(U3-SCLK{slash}SCL)") (class "Default")
      (node (ref "U3") (pin "23") (pinfunction "SCLK/SCL_23") (pintype "input"))
      (node (ref "U4") (pin "21") (pinfunction "PA5_-_SPI1_SCK_21") (pintype "bidirectional"))
    )
    (net (code "66") (name "Net-(U3-SDI{slash}SDA)") (class "Default")
      (node (ref "U3") (pin "24") (pinfunction "SDI/SDA_24") (pintype "bidirectional"))
      (node (ref "U4") (pin "23") (pinfunction "PA7_-_SPI1_MOSI_23") (pintype "bidirectional"))
    )
    (net (code "67") (name "Net-(U3-VDD)") (class "Default")
      (node (ref "C10") (pin "2") (pinfunction "2_2") (pintype "passive"))
      (node (ref "C11") (pin "1") (pinfunction "1_1") (pintype "passive"))
      (node (ref "L1") (pin "2") (pinfunction "2_2") (pintype "passive"))
      (node (ref "U3") (pin "13") (pinfunction "VDD_13") (pintype "power_in"))
    )
    (net (code "68") (name "Net-(U3-{slash}CS)") (class "Default")
      (node (ref "R2") (pin "2") (pinfunction "2_2") (pintype "passive"))
      (node (ref "U3") (pin "8") (pinfunction "/CS_8") (pintype "passive"))
      (node (ref "U4") (pin "20") (pinfunction "PA4_-_SPI1_NSS_20") (pintype "bidirectional"))
    )
    (net (code "69") (name "Net-(U4-BOOT0)") (class "Default")
      (node (ref "JP7") (pin "1") (pinfunction "1_1") (pintype "passive"))
      (node (ref "R13") (pin "1") (pinfunction "1_1") (pintype "passive"))
      (node (ref "U4") (pin "60") (pinfunction "BOOT0_60") (pintype "input"))
    )
    (net (code "70") (name "Net-(U4-OSC_IN{slash}PD0)") (class "Default")
      (node (ref "U4") (pin "5") (pinfunction "OSC_IN/PD0_5") (pintype "input"))
      (node (ref "X1") (pin "1") (pinfunction "1_1") (pintype "passive"))
    )
    (net (code "71") (name "Net-(U4-OSC_OUT{slash}PD1)") (class "Default")
      (node (ref "U4") (pin "6") (pinfunction "OSC_OUT/PD1_6") (pintype "output"))
      (node (ref "X1") (pin "2") (pinfunction "2_2") (pintype "passive"))
    )
    (net (code "72") (name "Net-(U4-PB3_-_Flash_CS)") (class "Default")
      (node (ref "R15") (pin "2") (pinfunction "2_2") (pintype "passive"))
      (node (ref "U4") (pin "55") (pinfunction "PB3_-_Flash_CS_55") (pintype "bidirectional"))
      (node (ref "U8") (pin "1") (pinfunction "~{CS}_1") (pintype "input"))
    )
    (net (code "73") (name "Net-(U4-PB7_-_Mag_DRDY)") (class "Default")
      (node (ref "U4") (pin "59") (pinfunction "PB7_-_Mag_DRDY_59") (pintype "bidirectional"))
      (node (ref "U6") (pin "15") (pinfunction "DRDY_15") (pintype "power_in"))
    )
    (net (code "74") (name "Net-(U4-PB8_-_I2C1_SCL)") (class "Default")
      (node (ref "R17") (pin "2") (pinfunction "2_2") (pintype "passive"))
      (node (ref "U4") (pin "61") (pinfunction "PB8_-_I2C1_SCL_61") (pintype "bidirectional"))
      (node (ref "U6") (pin "1") (pinfunction "SCL_1") (pintype "passive"))
      (node (ref "U7") (pin "8") (pinfunction "SCLK_8") (pintype "passive"))
    )
    (net (code "75") (name "Net-(U4-PB9_-_I2C1_SDA)") (class "Default")
      (node (ref "R16") (pin "2") (pinfunction "2_2") (pintype "passive"))
      (node (ref "U4") (pin "62") (pinfunction "PB9_-_I2C1_SDA_62") (pintype "bidirectional"))
      (node (ref "U6") (pin "16") (pinfunction "SDA_16") (pintype "passive"))
      (node (ref "U7") (pin "7") (pinfunction "SDA_7") (pintype "passive"))
    )
    (net (code "76") (name "Net-(U4-PB10-I2C2_SCL)") (class "Default")
      (node (ref "FIL7") (pin "3") (pinfunction "3_3") (pintype "passive"))
      (node (ref "R4") (pin "1") (pinfunction "1_1") (pintype "passive"))
      (node (ref "U4") (pin "29") (pinfunction "PB10-I2C2_SCL_29") (pintype "bidirectional"))
    )
    (net (code "77") (name "Net-(U4-PB11-I2C2_SDA)") (class "Default")
      (node (ref "FIL7") (pin "1") (pinfunction "1_1") (pintype "passive"))
      (node (ref "R3") (pin "1") (pinfunction "1_1") (pintype "passive"))
      (node (ref "U4") (pin "30") (pinfunction "PB11-I2C2_SDA_30") (pintype "bidirectional"))
    )
    (net (code "78") (name "Net-(U4-PB12)") (class "Default")
      (node (ref "FIL1") (pin "3") (pinfunction "3_3") (pintype "passive"))
      (node (ref "U4") (pin "33") (pinfunction "PB12_33") (pintype "bidirectional"))
    )
    (net (code "79") (name "Net-(U4-PB13)") (class "Default")
      (node (ref "FIL1") (pin "1") (pinfunction "1_1") (pintype "passive"))
      (node (ref "U4") (pin "34") (pinfunction "PB13_34") (pintype "bidirectional"))
    )
    (net (code "80") (name "Net-(U4-PC3_-_Frequency)") (class "Default")
      (node (ref "R22") (pin "2") (pinfunction "2_2") (pintype "passive"))
      (node (ref "U4") (pin "11") (pinfunction "PC3_-_Frequency_11") (pintype "bidirectional"))
    )
    (net (code "81") (name "Net-(U4-VCP_1)") (class "Default")
      (node (ref "C14") (pin "2") (pinfunction "2_2") (pintype "passive"))
      (node (ref "U4") (pin "31") (pinfunction "VCP_1_31") (pintype "power_in"))
    )
    (net (code "82") (name "Net-(U4-VCP_2)") (class "Default")
      (node (ref "C25") (pin "2") (pinfunction "2_2") (pintype "passive"))
      (node (ref "U4") (pin "47") (pinfunction "VCP_2_47") (pintype "power_in"))
    )
    (net (code "83") (name "Net-(U5-B)") (class "Default")
      (node (ref "FIL6") (pin "1") (pinfunction "1_1") (pintype "passive"))
      (node (ref "R9") (pin "2") (pinfunction "2_2") (pintype "passive"))
      (node (ref "U5") (pin "2") (pinfunction "B_2") (pintype "input"))
    )
    (net (code "84") (name "Net-(U6-C1)") (class "Default")
      (node (ref "C28") (pin "1") (pinfunction "1_1") (pintype "passive"))
      (node (ref "U6") (pin "10") (pinfunction "C1_10") (pintype "passive"))
    )
    (net (code "85") (name "Net-(U6-SETC)") (class "Default")
      (node (ref "C26") (pin "1") (pinfunction "1_1") (pintype "passive"))
      (node (ref "U6") (pin "12") (pinfunction "SETC_12") (pintype "power_in"))
    )
    (net (code "86") (name "Net-(U6-SETP)") (class "Default")
      (node (ref "C26") (pin "2") (pinfunction "2_2") (pintype "passive"))
      (node (ref "U6") (pin "8") (pinfunction "SETP_8") (pintype "passive"))
    )
    (net (code "87") (name "Net-(U7-PS)") (class "Default")
      (node (ref "C29") (pin "1") (pinfunction "1_1") (pintype "passive"))
      (node (ref "L3") (pin "1") (pinfunction "1_1") (pintype "passive"))
      (node (ref "U7") (pin "1") (pinfunction "VDD_1") (pintype "power_in"))
      (node (ref "U7") (pin "2") (pinfunction "PS_2") (pintype "passive"))
    )
    (net (code "88") (name "Net-(U9-BYPASS)") (class "Default")
      (node (ref "C34") (pin "1") (pinfunction "1_1") (pintype "passive"))
      (node (ref "U9") (pin "4") (pinfunction "BYPASS_4") (pintype "passive"))
    )
    (net (code "89") (name "TO_REGS") (class "Default")
      (node (ref "C2") (pin "1") (pinfunction "1_1") (pintype "passive"))
      (node (ref "C33") (pin "2") (pinfunction "2_2") (pintype "passive"))
      (node (ref "C35") (pin "1") (pinfunction "1_1") (pintype "passive"))
      (node (ref "C36") (pin "1") (pinfunction "1_1") (pintype "passive"))
      (node (ref "C5") (pin "1") (pinfunction "1_1") (pintype "passive"))
      (node (ref "C6") (pin "1") (pinfunction "1_1") (pintype "passive"))
      (node (ref "L4") (pin "1") (pinfunction "1_1") (pintype "passive"))
      (node (ref "U1") (pin "1") (pinfunction "VIN_1") (pintype "power_in"))
      (node (ref "U1") (pin "3") (pinfunction "ON/OFF_3") (pintype "input"))
      (node (ref "U2") (pin "1") (pinfunction "VIN_1") (pintype "power_in"))
      (node (ref "U2") (pin "3") (pinfunction "ON/OFF_3") (pintype "input"))
      (node (ref "U9") (pin "1") (pinfunction "VIN_1") (pintype "power_in"))
      (node (ref "U9") (pin "3") (pinfunction "ON/OFF_3") (pintype "input"))
    )
    (net (code "90") (name "VCC") (class "Default")
      (node (ref "C1") (pin "1") (pinfunction "1_1") (pintype "passive"))
      (node (ref "C15") (pin "1") (pinfunction "1_1") (pintype "passive"))
      (node (ref "C16") (pin "2") (pinfunction "2_2") (pintype "passive"))
      (node (ref "C17") (pin "2") (pinfunction "2_2") (pintype "passive"))
      (node (ref "C18") (pin "1") (pinfunction "1_1") (pintype "passive"))
      (node (ref "C20") (pin "2") (pinfunction "2_2") (pintype "passive"))
      (node (ref "C21") (pin "1") (pinfunction "1_1") (pintype "passive"))
      (node (ref "C22") (pin "2") (pinfunction "2_2") (pintype "passive"))
      (node (ref "C23") (pin "1") (pinfunction "1_1") (pintype "passive"))
      (node (ref "C24") (pin "2") (pinfunction "2_2") (pintype "passive"))
      (node (ref "C27") (pin "1") (pinfunction "1_1") (pintype "passive"))
      (node (ref "C3") (pin "1") (pinfunction "1_1") (pintype "passive"))
      (node (ref "C32") (pin "1") (pinfunction "1_1") (pintype "passive"))
      (node (ref "D2") (pin "2") (pinfunction "A_2") (pintype "passive"))
      (node (ref "D3") (pin "2") (pinfunction "A_2") (pintype "passive"))
      (node (ref "D4") (pin "2") (pinfunction "A_2") (pintype "passive"))
      (node (ref "JP7") (pin "2") (pinfunction "2_2") (pintype "passive"))
      (node (ref "R15") (pin "1") (pinfunction "1_1") (pintype "passive"))
      (node (ref "R16") (pin "1") (pinfunction "1_1") (pintype "passive"))
      (node (ref "R17") (pin "1") (pinfunction "1_1") (pintype "passive"))
      (node (ref "R18") (pin "1") (pinfunction "1_1") (pintype "passive"))
      (node (ref "R19") (pin "2") (pinfunction "2_2") (pintype "passive"))
      (node (ref "R2") (pin "1") (pinfunction "1_1") (pintype "passive"))
      (node (ref "R22") (pin "1") (pinfunction "1_1") (pintype "passive"))
      (node (ref "R3") (pin "2") (pinfunction "2_2") (pintype "passive"))
      (node (ref "R4") (pin "2") (pinfunction "2_2") (pintype "passive"))
      (node (ref "R8") (pin "2") (pinfunction "2_2") (pintype "passive"))
      (node (ref "U1") (pin "5") (pinfunction "VOUT_5") (pintype "power_in"))
      (node (ref "U4") (pin "1") (pinfunction "VBAT_1") (pintype "power_in"))
      (node (ref "U4") (pin "13") (pinfunction "VDDA_13") (pintype "power_in"))
      (node (ref "U4") (pin "19") (pinfunction "VDD_4_19") (pintype "power_in"))
      (node (ref "U4") (pin "32") (pinfunction "VDD_1_32") (pintype "power_in"))
      (node (ref "U4") (pin "48") (pinfunction "VDD_2_48") (pintype "power_in"))
      (node (ref "U4") (pin "64") (pinfunction "VDD_3_64") (pintype "power_in"))
      (node (ref "U5") (pin "5") (pinfunction "VCC_5") (pintype "power_in"))
      (node (ref "U6") (pin "13") (pinfunction "VddIO_13") (pintype "passive"))
      (node (ref "U6") (pin "2") (pinfunction "Vdd_2") (pintype "power_in"))
      (node (ref "U6") (pin "4") (pinfunction "S1_4") (pintype "passive"))
      (node (ref "U8") (pin "3") (pinfunction "~{WP}_3") (pintype "input"))
      (node (ref "U8") (pin "7") (pinfunction "~{HOLD}_7") (pintype "input"))
      (node (ref "U8") (pin "8") (pinfunction "VCC_8") (pintype "power_in"))
    )
    (net (code "91") (name "VCC_ANA") (class "Default")
      (node (ref "C4") (pin "1") (pinfunction "1_1") (pintype "passive"))
      (node (ref "C7") (pin "1") (pinfunction "1_1") (pintype "passive"))
      (node (ref "L1") (pin "1") (pinfunction "1_1") (pintype "passive"))
      (node (ref "L3") (pin "2") (pinfunction "2_2") (pintype "passive"))
      (node (ref "U2") (pin "5") (pinfunction "VOUT_5") (pintype "power_in"))
    )
    (net (code "92") (name "VCC_UNREG") (class "Default")
      (node (ref "CONN1") (pin "2") (pinfunction "2_2") (pintype "passive"))
      (node (ref "CONN2") (pin "2") (pinfunction "2_2") (pintype "passive"))
      (node (ref "CONN3") (pin "2") (pinfunction "2_2") (pintype "passive"))
      (node (ref "CONN4") (pin "2") (pinfunction "2_2") (pintype "passive"))
      (node (ref "D1") (pin "2") (pinfunction "A2_2") (pintype "passive"))
      (node (ref "JP1") (pin "2") (pinfunction "+_2") (pintype "passive"))
      (node (ref "JP2") (pin "2") (pinfunction "+_2") (pintype "passive"))
      (node (ref "JP3") (pin "2") (pinfunction "+_2") (pintype "passive"))
      (node (ref "JP4") (pin "2") (pinfunction "+_2") (pintype "passive"))
      (node (ref "JP5") (pin "2") (pinfunction "+_2") (pintype "passive"))
      (node (ref "JP6") (pin "2") (pinfunction "+_2") (pintype "passive"))
    )
    (net (code "93") (name "unconnected-(CONN5-ID-Pad4)") (class "Default")
      (node (ref "CONN5") (pin "4") (pinfunction "ID_4") (pintype "passive"))
    )
    (net (code "94") (name "unconnected-(RF1-GPIO_2-Pad8)") (class "Default")
      (node (ref "RF1") (pin "8") (pinfunction "GPIO_2_8") (pintype "bidirectional"))
    )
    (net (code "95") (name "unconnected-(RF1-N.C-Pad1)") (class "Default")
      (node (ref "RF1") (pin "1") (pinfunction "N.C_1") (pintype "tri_state"))
    )
    (net (code "96") (name "unconnected-(RF1-N.C-Pad4)") (class "Default")
      (node (ref "RF1") (pin "4") (pinfunction "N.C_4") (pintype "tri_state"))
    )
    (net (code "97") (name "unconnected-(RF1-N.C-Pad8)") (class "Default")
      (node (ref "RF1") (pin "8") (pinfunction "N.C_8") (pintype "tri_state"))
    )
    (net (code "98") (name "unconnected-(RF1-N.C-Pad9)") (class "Default")
      (node (ref "RF1") (pin "9") (pinfunction "N.C_9") (pintype "tri_state"))
    )
    (net (code "99") (name "unconnected-(RF1-N.C-Pad14)") (class "Default")
      (node (ref "RF1") (pin "14") (pinfunction "N.C_14") (pintype "tri_state"))
    )
    (net (code "100") (name "unconnected-(U3-AUX_CL-Pad7)") (class "Default")
      (node (ref "U3") (pin "7") (pinfunction "AUX_CL_7") (pintype "bidirectional"))
    )
    (net (code "101") (name "unconnected-(U3-AUX_DA-Pad6)") (class "Default")
      (node (ref "U3") (pin "6") (pinfunction "AUX_DA_6") (pintype "bidirectional"))
    )
    (net (code "102") (name "unconnected-(U3-CLKOUT-Pad22)") (class "Default")
      (node (ref "U3") (pin "22") (pinfunction "CLKOUT_22") (pintype "output"))
    )
    (net (code "103") (name "unconnected-(U3-NC-Pad2)") (class "Default")
      (node (ref "U3") (pin "2") (pinfunction "NC_2") (pintype "tri_state"))
    )
    (net (code "104") (name "unconnected-(U3-NC-Pad3)") (class "Default")
      (node (ref "U3") (pin "3") (pinfunction "NC_3") (pintype "tri_state"))
    )
    (net (code "105") (name "unconnected-(U3-NC-Pad4)") (class "Default")
      (node (ref "U3") (pin "4") (pinfunction "NC_4") (pintype "tri_state"))
    )
    (net (code "106") (name "unconnected-(U3-NC-Pad5)") (class "Default")
      (node (ref "U3") (pin "5") (pinfunction "NC_5") (pintype "tri_state"))
    )
    (net (code "107") (name "unconnected-(U3-NC-Pad14)") (class "Default")
      (node (ref "U3") (pin "14") (pinfunction "NC_14") (pintype "bidirectional"))
    )
    (net (code "108") (name "unconnected-(U3-NC-Pad15)") (class "Default")
      (node (ref "U3") (pin "15") (pinfunction "NC_15") (pintype "tri_state"))
    )
    (net (code "109") (name "unconnected-(U3-NC-Pad16)") (class "Default")
      (node (ref "U3") (pin "16") (pinfunction "NC_16") (pintype "tri_state"))
    )
    (net (code "110") (name "unconnected-(U3-NC-Pad17)") (class "Default")
      (node (ref "U3") (pin "17") (pinfunction "NC_17") (pintype "tri_state"))
    )
    (net (code "111") (name "unconnected-(U3-RESV-Pad19)") (class "Default")
      (node (ref "U3") (pin "19") (pinfunction "RESV_19") (pintype "passive"))
    )
    (net (code "112") (name "unconnected-(U3-RESV-Pad21)") (class "Default")
      (node (ref "U3") (pin "21") (pinfunction "RESV_21") (pintype "passive"))
    )
    (net (code "113") (name "unconnected-(U4-PB6_--Pad58)") (class "Default")
      (node (ref "U4") (pin "58") (pinfunction "PB6_-_58") (pintype "bidirectional"))
    )
    (net (code "114") (name "unconnected-(U4-PC13_-_RTC-Pad2)") (class "Default")
      (node (ref "U4") (pin "2") (pinfunction "PC13_-_RTC_2") (pintype "bidirectional"))
    )
    (net (code "115") (name "unconnected-(U4-PC14-OSC32_IN-Pad3)") (class "Default")
      (node (ref "U4") (pin "3") (pinfunction "PC14-OSC32_IN_3") (pintype "bidirectional"))
    )
    (net (code "116") (name "unconnected-(U4-PC15-OSC32_OUT-Pad4)") (class "Default")
      (node (ref "U4") (pin "4") (pinfunction "PC15-OSC32_OUT_4") (pintype "bidirectional"))
    )
    (net (code "117") (name "unconnected-(U6-NC-Pad3)") (class "Default")
      (node (ref "U6") (pin "3") (pinfunction "NC_3") (pintype "passive"))
    )
    (net (code "118") (name "unconnected-(U6-NC-Pad5)") (class "Default")
      (node (ref "U6") (pin "5") (pinfunction "NC_5") (pintype "passive"))
    )
    (net (code "119") (name "unconnected-(U6-NC-Pad6)") (class "Default")
      (node (ref "U6") (pin "6") (pinfunction "NC_6") (pintype "passive"))
    )
    (net (code "120") (name "unconnected-(U6-NC-Pad7)") (class "Default")
      (node (ref "U6") (pin "7") (pinfunction "NC_7") (pintype "passive"))
    )
    (net (code "121") (name "unconnected-(U6-NC-Pad8)") (class "Default")
      (node (ref "U6") (pin "8") (pinfunction "NC_8") (pintype "passive"))
    )
    (net (code "122") (name "unconnected-(U6-NC-Pad14)") (class "Default")
      (node (ref "U6") (pin "14") (pinfunction "NC_14") (pintype "passive"))
    )
    (net (code "123") (name "unconnected-(U7-CSB-Pad5)") (class "Default")
      (node (ref "U7") (pin "5") (pinfunction "CSB_5") (pintype "passive"))
    )
    (net (code "124") (name "unconnected-(U7-SDO-Pad6)") (class "Default")
      (node (ref "U7") (pin "6") (pinfunction "SDO_6") (pintype "passive"))
    )
  )
)
